# Programmer_Interface.net
KiCad netlist of a schematic drawn in Altium Designer
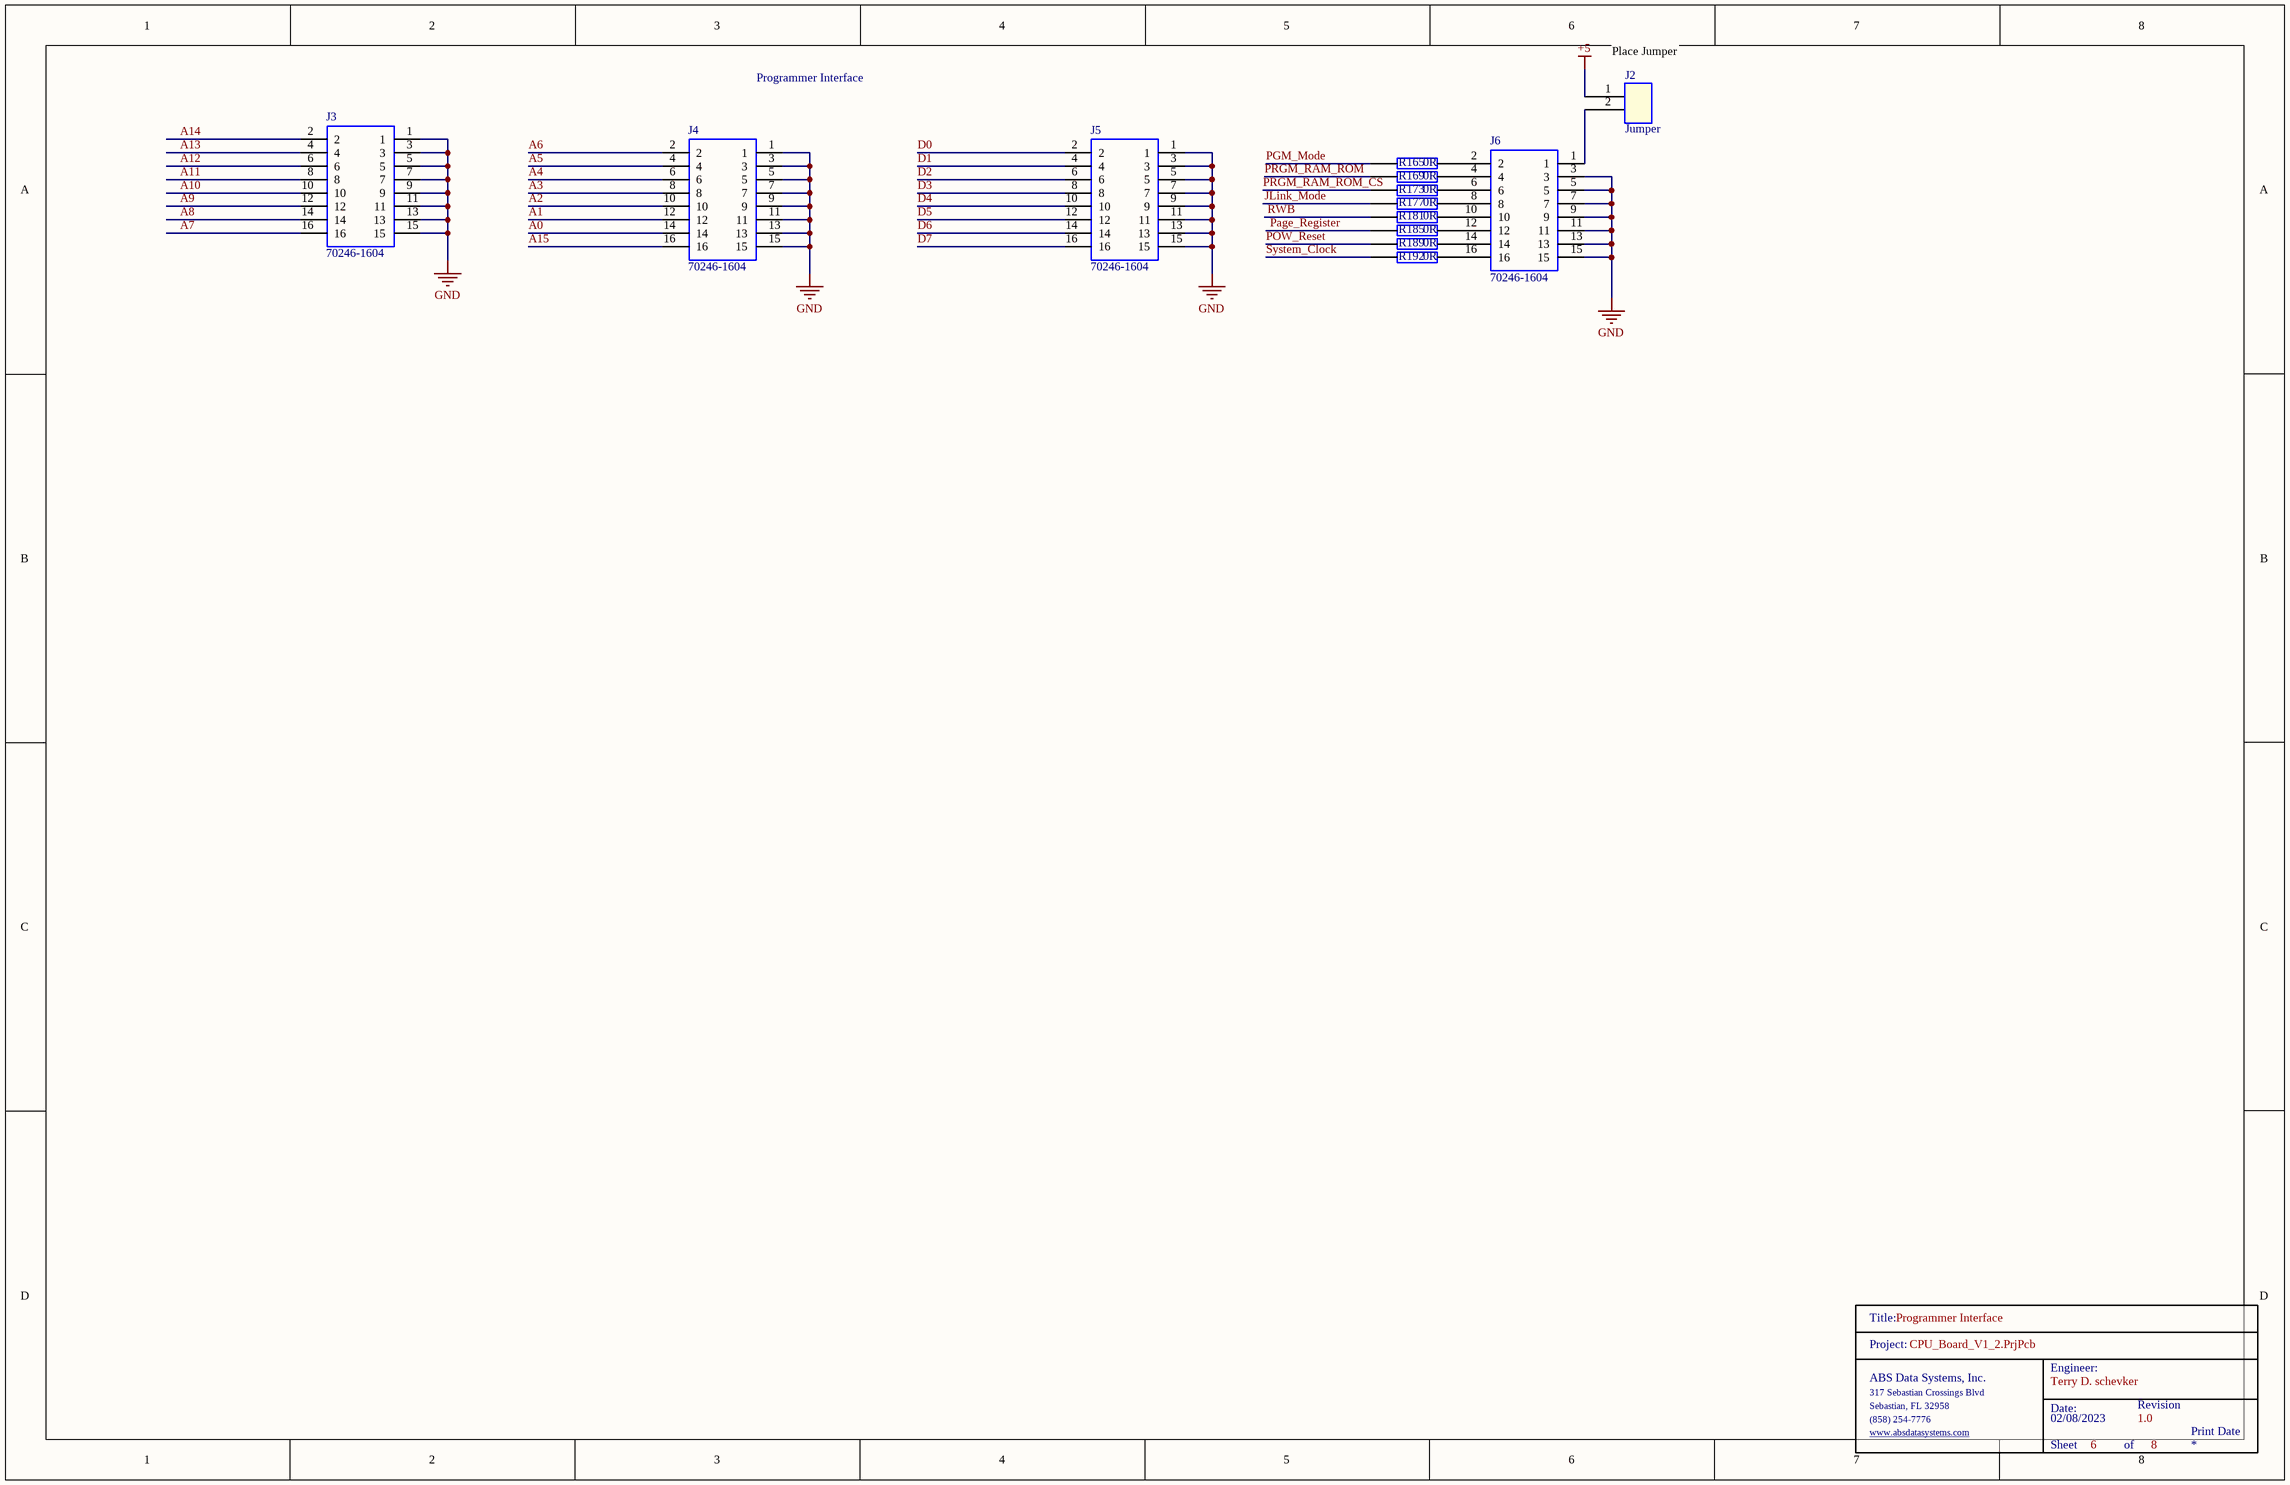
[diagram p0: Programmer_Interface.SchDoc]

(export (version "E")
  (design (tool "Eeschema 10.0.6"))
  (components
    (comp (ref "J2")
      (value "Jumper")
      (footprint "Jumper")
      (description "16 Pin 3x8 Through Hold Jumprts")
      (fields
        (field (name "MANUFACTURER") "Samtec")
        (field (name "MANUFACTURER PART NUMBER") "TST-108-01-G-D")
      )
      (libsource (lib "Misc") (part "Jumper"))
    )
    (comp (ref "J3")
      (value "70246-1604")
      (footprint "SHDR16W99P254_2X8_2794X889X927P")
      (description "Molex C-GRID 70246, 2.54mm Pitch, 16 Way, 2 Row, Straight PCB Header, Through Hole")
      (fields (field (name "MOUSER PART NUMBER") "538-70246-1604"))
      (libsource (lib "Connectors") (part "70246-1604"))
    )
    (comp (ref "J4")
      (value "70246-1604")
      (footprint "SHDR16W99P254_2X8_2794X889X927P")
      (description "Molex C-GRID 70246, 2.54mm Pitch, 16 Way, 2 Row, Straight PCB Header, Through Hole")
      (fields (field (name "MOUSER PART NUMBER") "538-70246-1604"))
      (libsource (lib "Connectors") (part "70246-1604"))
    )
    (comp (ref "J5")
      (value "70246-1604")
      (footprint "SHDR16W99P254_2X8_2794X889X927P")
      (description "Molex C-GRID 70246, 2.54mm Pitch, 16 Way, 2 Row, Straight PCB Header, Through Hole")
      (fields (field (name "MOUSER PART NUMBER") "538-70246-1604"))
      (libsource (lib "Connectors") (part "70246-1604"))
    )
    (comp (ref "J6")
      (value "70246-1604")
      (footprint "SHDR16W99P254_2X8_2794X889X927P")
      (description "Molex C-GRID 70246, 2.54mm Pitch, 16 Way, 2 Row, Straight PCB Header, Through Hole")
      (fields (field (name "MOUSER PART NUMBER") "538-70246-1604"))
      (libsource (lib "Connectors") (part "70246-1604"))
    )
    (comp (ref "R165")
      (value "0R")
      (footprint "0603")
      (description "YAGEO 0603 0 ohm")
      (fields
        (field (name "MOUSER PART NUMBER") "603-RC0603JR-070RL")
        (field (name "MANUFACTURER_PART_NUMBER") "RC0603JR-070RL")
      )
      (libsource (lib "Resistors") (part "RC0603JR-070RL"))
    )
    (comp (ref "R169")
      (value "0R")
      (footprint "0603")
      (description "YAGEO 0603 0 ohm")
      (fields
        (field (name "MOUSER PART NUMBER") "603-RC0603JR-070RL")
        (field (name "MANUFACTURER_PART_NUMBER") "RC0603JR-070RL")
      )
      (libsource (lib "Resistors") (part "RC0603JR-070RL"))
    )
    (comp (ref "R173")
      (value "0R")
      (footprint "0603")
      (description "YAGEO 0603 0 ohm")
      (fields
        (field (name "MOUSER PART NUMBER") "603-RC0603JR-070RL")
        (field (name "MANUFACTURER_PART_NUMBER") "RC0603JR-070RL")
      )
      (libsource (lib "Resistors") (part "RC0603JR-070RL"))
    )
    (comp (ref "R177")
      (value "0R")
      (footprint "0603")
      (description "YAGEO 0603 0 ohm")
      (fields
        (field (name "MOUSER PART NUMBER") "603-RC0603JR-070RL")
        (field (name "MANUFACTURER_PART_NUMBER") "RC0603JR-070RL")
      )
      (libsource (lib "Resistors") (part "RC0603JR-070RL"))
    )
    (comp (ref "R181")
      (value "0R")
      (footprint "0603")
      (description "YAGEO 0603 0 ohm")
      (fields
        (field (name "MOUSER PART NUMBER") "603-RC0603JR-070RL")
        (field (name "MANUFACTURER_PART_NUMBER") "RC0603JR-070RL")
      )
      (libsource (lib "Resistors") (part "RC0603JR-070RL"))
    )
    (comp (ref "R185")
      (value "0R")
      (footprint "0603")
      (description "YAGEO 0603 0 ohm")
      (fields
        (field (name "MOUSER PART NUMBER") "603-RC0603JR-070RL")
        (field (name "MANUFACTURER_PART_NUMBER") "RC0603JR-070RL")
      )
      (libsource (lib "Resistors") (part "RC0603JR-070RL"))
    )
    (comp (ref "R189")
      (value "0R")
      (footprint "0603")
      (description "YAGEO 0603 0 ohm")
      (fields
        (field (name "MOUSER PART NUMBER") "603-RC0603JR-070RL")
        (field (name "MANUFACTURER_PART_NUMBER") "RC0603JR-070RL")
      )
      (libsource (lib "Resistors") (part "RC0603JR-070RL"))
    )
    (comp (ref "R192")
      (value "0R")
      (footprint "0603")
      (description "YAGEO 0603 0 ohm")
      (fields
        (field (name "MOUSER PART NUMBER") "603-RC0603JR-070RL")
        (field (name "MANUFACTURER_PART_NUMBER") "RC0603JR-070RL")
      )
      (libsource (lib "Resistors") (part "RC0603JR-070RL"))
    )
    (comp (ref "TitleBlock_4") (value "TitleBlock") (libsource (lib "Misc") (part "TitleBlock")))
  )
  (nets
    (net (code "1") (name "+5") (class "Default")
      (node (ref "J2") (pin "1") (pinfunction "1_1") (pintype "passive"))
    )
    (net (code "2") (name "/A0") (class "Default")
      (node (ref "J4") (pin "14") (pinfunction "14_14") (pintype "passive"))
    )
    (net (code "3") (name "/A1") (class "Default")
      (node (ref "J4") (pin "12") (pinfunction "12_12") (pintype "passive"))
    )
    (net (code "4") (name "/A2") (class "Default")
      (node (ref "J4") (pin "10") (pinfunction "10_10") (pintype "passive"))
    )
    (net (code "5") (name "/A3") (class "Default")
      (node (ref "J4") (pin "8") (pinfunction "8_8") (pintype "passive"))
    )
    (net (code "6") (name "/A4") (class "Default")
      (node (ref "J4") (pin "6") (pinfunction "6_6") (pintype "passive"))
    )
    (net (code "7") (name "/A5") (class "Default")
      (node (ref "J4") (pin "4") (pinfunction "4_4") (pintype "passive"))
    )
    (net (code "8") (name "/A6") (class "Default")
      (node (ref "J4") (pin "2") (pinfunction "2_2") (pintype "passive"))
    )
    (net (code "9") (name "/A7") (class "Default")
      (node (ref "J3") (pin "16") (pinfunction "16_16") (pintype "passive"))
    )
    (net (code "10") (name "/A8") (class "Default")
      (node (ref "J3") (pin "14") (pinfunction "14_14") (pintype "passive"))
    )
    (net (code "11") (name "/A9") (class "Default")
      (node (ref "J3") (pin "12") (pinfunction "12_12") (pintype "passive"))
    )
    (net (code "12") (name "/A10") (class "Default")
      (node (ref "J3") (pin "10") (pinfunction "10_10") (pintype "passive"))
    )
    (net (code "13") (name "/A11") (class "Default")
      (node (ref "J3") (pin "8") (pinfunction "8_8") (pintype "passive"))
    )
    (net (code "14") (name "/A12") (class "Default")
      (node (ref "J3") (pin "6") (pinfunction "6_6") (pintype "passive"))
    )
    (net (code "15") (name "/A13") (class "Default")
      (node (ref "J3") (pin "4") (pinfunction "4_4") (pintype "passive"))
    )
    (net (code "16") (name "/A14") (class "Default")
      (node (ref "J3") (pin "2") (pinfunction "2_2") (pintype "passive"))
    )
    (net (code "17") (name "/A15") (class "Default")
      (node (ref "J4") (pin "16") (pinfunction "16_16") (pintype "passive"))
    )
    (net (code "18") (name "/D0") (class "Default")
      (node (ref "J5") (pin "2") (pinfunction "2_2") (pintype "passive"))
    )
    (net (code "19") (name "/D1") (class "Default")
      (node (ref "J5") (pin "4") (pinfunction "4_4") (pintype "passive"))
    )
    (net (code "20") (name "/D2") (class "Default")
      (node (ref "J5") (pin "6") (pinfunction "6_6") (pintype "passive"))
    )
    (net (code "21") (name "/D3") (class "Default")
      (node (ref "J5") (pin "8") (pinfunction "8_8") (pintype "passive"))
    )
    (net (code "22") (name "/D4") (class "Default")
      (node (ref "J5") (pin "10") (pinfunction "10_10") (pintype "passive"))
    )
    (net (code "23") (name "/D5") (class "Default")
      (node (ref "J5") (pin "12") (pinfunction "12_12") (pintype "passive"))
    )
    (net (code "24") (name "/D6") (class "Default")
      (node (ref "J5") (pin "14") (pinfunction "14_14") (pintype "passive"))
    )
    (net (code "25") (name "/D7") (class "Default")
      (node (ref "J5") (pin "16") (pinfunction "16_16") (pintype "passive"))
    )
    (net (code "26") (name "/JLink_Mode") (class "Default")
      (node (ref "R177") (pin "1") (pinfunction "1_1") (pintype "passive"))
    )
    (net (code "27") (name "/PGM_Mode") (class "Default")
      (node (ref "R165") (pin "1") (pinfunction "1_1") (pintype "passive"))
    )
    (net (code "28") (name "/POW_Reset") (class "Default")
      (node (ref "R189") (pin "1") (pinfunction "1_1") (pintype "passive"))
    )
    (net (code "29") (name "/PRGM_RAM_ROM") (class "Default")
      (node (ref "R169") (pin "1") (pinfunction "1_1") (pintype "passive"))
    )
    (net (code "30") (name "/PRGM_RAM_ROM_CS") (class "Default")
      (node (ref "R173") (pin "1") (pinfunction "1_1") (pintype "passive"))
    )
    (net (code "31") (name "/Page_Register") (class "Default")
      (node (ref "R185") (pin "1") (pinfunction "1_1") (pintype "passive"))
    )
    (net (code "32") (name "/RWB") (class "Default")
      (node (ref "R181") (pin "1") (pinfunction "1_1") (pintype "passive"))
    )
    (net (code "33") (name "/System_Clock") (class "Default")
      (node (ref "R192") (pin "1") (pinfunction "1_1") (pintype "passive"))
    )
    (net (code "34") (name "GND") (class "Default")
      (node (ref "J3") (pin "1") (pinfunction "1_1") (pintype "passive"))
      (node (ref "J3") (pin "11") (pinfunction "11_11") (pintype "passive"))
      (node (ref "J3") (pin "13") (pinfunction "13_13") (pintype "passive"))
      (node (ref "J3") (pin "15") (pinfunction "15_15") (pintype "passive"))
      (node (ref "J3") (pin "3") (pinfunction "3_3") (pintype "passive"))
      (node (ref "J3") (pin "5") (pinfunction "5_5") (pintype "passive"))
      (node (ref "J3") (pin "7") (pinfunction "7_7") (pintype "passive"))
      (node (ref "J3") (pin "9") (pinfunction "9_9") (pintype "passive"))
      (node (ref "J4") (pin "1") (pinfunction "1_1") (pintype "passive"))
      (node (ref "J4") (pin "11") (pinfunction "11_11") (pintype "passive"))
      (node (ref "J4") (pin "13") (pinfunction "13_13") (pintype "passive"))
      (node (ref "J4") (pin "15") (pinfunction "15_15") (pintype "passive"))
      (node (ref "J4") (pin "3") (pinfunction "3_3") (pintype "passive"))
      (node (ref "J4") (pin "5") (pinfunction "5_5") (pintype "passive"))
      (node (ref "J4") (pin "7") (pinfunction "7_7") (pintype "passive"))
      (node (ref "J4") (pin "9") (pinfunction "9_9") (pintype "passive"))
      (node (ref "J5") (pin "1") (pinfunction "1_1") (pintype "passive"))
      (node (ref "J5") (pin "11") (pinfunction "11_11") (pintype "passive"))
      (node (ref "J5") (pin "13") (pinfunction "13_13") (pintype "passive"))
      (node (ref "J5") (pin "15") (pinfunction "15_15") (pintype "passive"))
      (node (ref "J5") (pin "3") (pinfunction "3_3") (pintype "passive"))
      (node (ref "J5") (pin "5") (pinfunction "5_5") (pintype "passive"))
      (node (ref "J5") (pin "7") (pinfunction "7_7") (pintype "passive"))
      (node (ref "J5") (pin "9") (pinfunction "9_9") (pintype "passive"))
      (node (ref "J6") (pin "11") (pinfunction "11_11") (pintype "passive"))
      (node (ref "J6") (pin "13") (pinfunction "13_13") (pintype "passive"))
      (node (ref "J6") (pin "15") (pinfunction "15_15") (pintype "passive"))
      (node (ref "J6") (pin "3") (pinfunction "3_3") (pintype "passive"))
      (node (ref "J6") (pin "5") (pinfunction "5_5") (pintype "passive"))
      (node (ref "J6") (pin "7") (pinfunction "7_7") (pintype "passive"))
      (node (ref "J6") (pin "9") (pinfunction "9_9") (pintype "passive"))
    )
    (net (code "35") (name "Net-(J2-Pad2)") (class "Default")
      (node (ref "J2") (pin "2") (pinfunction "2_2") (pintype "passive"))
      (node (ref "J6") (pin "1") (pinfunction "1_1") (pintype "passive"))
    )
    (net (code "36") (name "Net-(J6-Pad2)") (class "Default")
      (node (ref "J6") (pin "2") (pinfunction "2_2") (pintype "passive"))
      (node (ref "R165") (pin "2") (pinfunction "2_2") (pintype "passive"))
    )
    (net (code "37") (name "Net-(J6-Pad4)") (class "Default")
      (node (ref "J6") (pin "4") (pinfunction "4_4") (pintype "passive"))
      (node (ref "R169") (pin "2") (pinfunction "2_2") (pintype "passive"))
    )
    (net (code "38") (name "Net-(J6-Pad6)") (class "Default")
      (node (ref "J6") (pin "6") (pinfunction "6_6") (pintype "passive"))
      (node (ref "R173") (pin "2") (pinfunction "2_2") (pintype "passive"))
    )
    (net (code "39") (name "Net-(J6-Pad8)") (class "Default")
      (node (ref "J6") (pin "8") (pinfunction "8_8") (pintype "passive"))
      (node (ref "R177") (pin "2") (pinfunction "2_2") (pintype "passive"))
    )
    (net (code "40") (name "Net-(J6-Pad10)") (class "Default")
      (node (ref "J6") (pin "10") (pinfunction "10_10") (pintype "passive"))
      (node (ref "R181") (pin "2") (pinfunction "2_2") (pintype "passive"))
    )
    (net (code "41") (name "Net-(J6-Pad12)") (class "Default")
      (node (ref "J6") (pin "12") (pinfunction "12_12") (pintype "passive"))
      (node (ref "R185") (pin "2") (pinfunction "2_2") (pintype "passive"))
    )
    (net (code "42") (name "Net-(J6-Pad14)") (class "Default")
      (node (ref "J6") (pin "14") (pinfunction "14_14") (pintype "passive"))
      (node (ref "R189") (pin "2") (pinfunction "2_2") (pintype "passive"))
    )
    (net (code "43") (name "Net-(J6-Pad16)") (class "Default")
      (node (ref "J6") (pin "16") (pinfunction "16_16") (pintype "passive"))
      (node (ref "R192") (pin "2") (pinfunction "2_2") (pintype "passive"))
    )
  )
)
